# accelerometer.net
KiCad netlist of a schematic drawn in Altium Designer
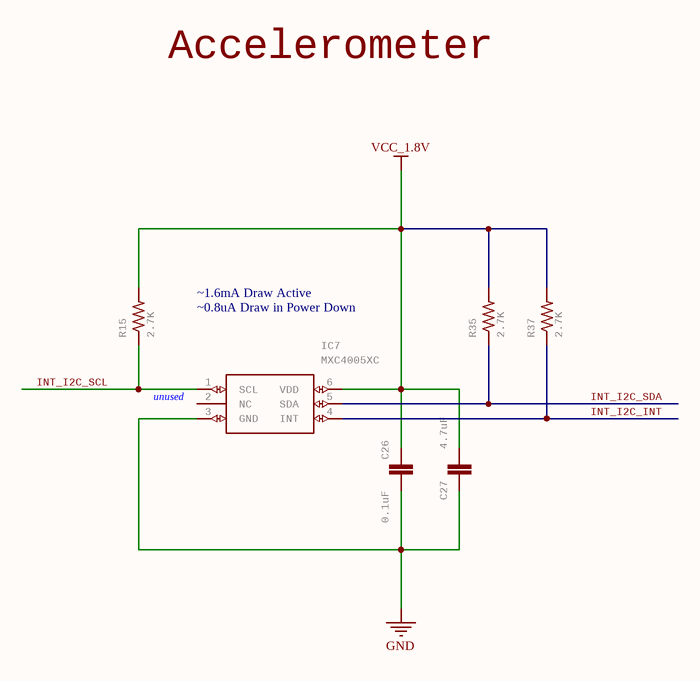
[diagram p0: accelerometer.SchDoc]

(export (version "E")
  (design (tool "Eeschema 10.0.6"))
  (components
    (comp (ref "C26")
      (value "0.1uF")
      (footprint "0402-CAP")
      (description "CAPACITOR, European symbol")
      (fields (field (name "MPN") "C0402C104Z4VAC"))
      (libsource (lib "openmv-ae3") (part "C-EUC0201"))
    )
    (comp (ref "C27")
      (value "4.7uF")
      (footprint "0402-CAP")
      (description "CapacitorStandard 0603 ceramic capacitor, and 0.1\" leaded capacitor.")
      (fields (field (name "MPN") "JMK105BBJ475MV-F") (field (name "LIBRARYNAME") "sfe"))
      (libsource (lib "openmv-ae3") (part "CAP0402-CAP"))
    )
    (comp (ref "IC7")
      (value "MXC4005XC")
      (footprint "MXC4005XC")
      (description "Accelerometers Monolithic and Wafer Level Packaged Three-Axis Accelerometer   Source:  Datasheet")
      (fields (field (name "MOUSER_PART_NUMBER") "438-MXC4005XC"))
      (libsource (lib "openmv-ae3") (part "MXC4005XC"))
    )
    (comp (ref "R15")
      (value "2.7K")
      (footprint "R0201")
      (fields (field (name "LIBRARYNAME") "sfe"))
      (libsource (lib "openmv-ae3") (part "RESISTOR0402-RES"))
    )
    (comp (ref "R35")
      (value "2.7K")
      (footprint "R0201")
      (fields (field (name "LIBRARYNAME") "sfe"))
      (libsource (lib "openmv-ae3") (part "RESISTOR0402-RES"))
    )
    (comp (ref "R37")
      (value "2.7K")
      (footprint "R0201")
      (fields (field (name "LIBRARYNAME") "sfe"))
      (libsource (lib "openmv-ae3") (part "RESISTOR0402-RES"))
    )
  )
  (nets
    (net (code "1") (name "/INT_I2C_INT") (class "Default")
      (node (ref "IC7") (pin "4") (pinfunction "INT_4") (pintype "bidirectional"))
      (node (ref "R37") (pin "1") (pinfunction "1_1") (pintype "passive"))
    )
    (net (code "2") (name "/INT_I2C_SCL") (class "Default")
      (node (ref "IC7") (pin "1") (pinfunction "SCL_1") (pintype "bidirectional"))
      (node (ref "R15") (pin "1") (pinfunction "1_1") (pintype "passive"))
    )
    (net (code "3") (name "/INT_I2C_SDA") (class "Default")
      (node (ref "IC7") (pin "5") (pinfunction "SDA_5") (pintype "bidirectional"))
      (node (ref "R35") (pin "1") (pinfunction "1_1") (pintype "passive"))
    )
    (net (code "4") (name "GND") (class "Default")
      (node (ref "C26") (pin "2") (pinfunction "2_2") (pintype "passive"))
      (node (ref "C27") (pin "1") (pinfunction "1_1") (pintype "passive"))
      (node (ref "IC7") (pin "3") (pinfunction "GND_3") (pintype "bidirectional"))
    )
    (net (code "5") (name "VCC_1.8V") (class "Default")
      (node (ref "C26") (pin "1") (pinfunction "1_1") (pintype "passive"))
      (node (ref "C27") (pin "2") (pinfunction "2_2") (pintype "passive"))
      (node (ref "IC7") (pin "6") (pinfunction "VDD_6") (pintype "bidirectional"))
      (node (ref "R15") (pin "2") (pinfunction "2_2") (pintype "passive"))
      (node (ref "R35") (pin "2") (pinfunction "2_2") (pintype "passive"))
      (node (ref "R37") (pin "2") (pinfunction "2_2") (pintype "passive"))
    )
    (net (code "6") (name "unconnected-(IC7-NC-Pad2)") (class "Default")
      (node (ref "IC7") (pin "2") (pinfunction "NC_2") (pintype "passive"))
    )
  )
)
